# Callisto_Teknic_MSO_LSI_Relay_x_4.net
KiCad netlist of a schematic drawn in EAGLE
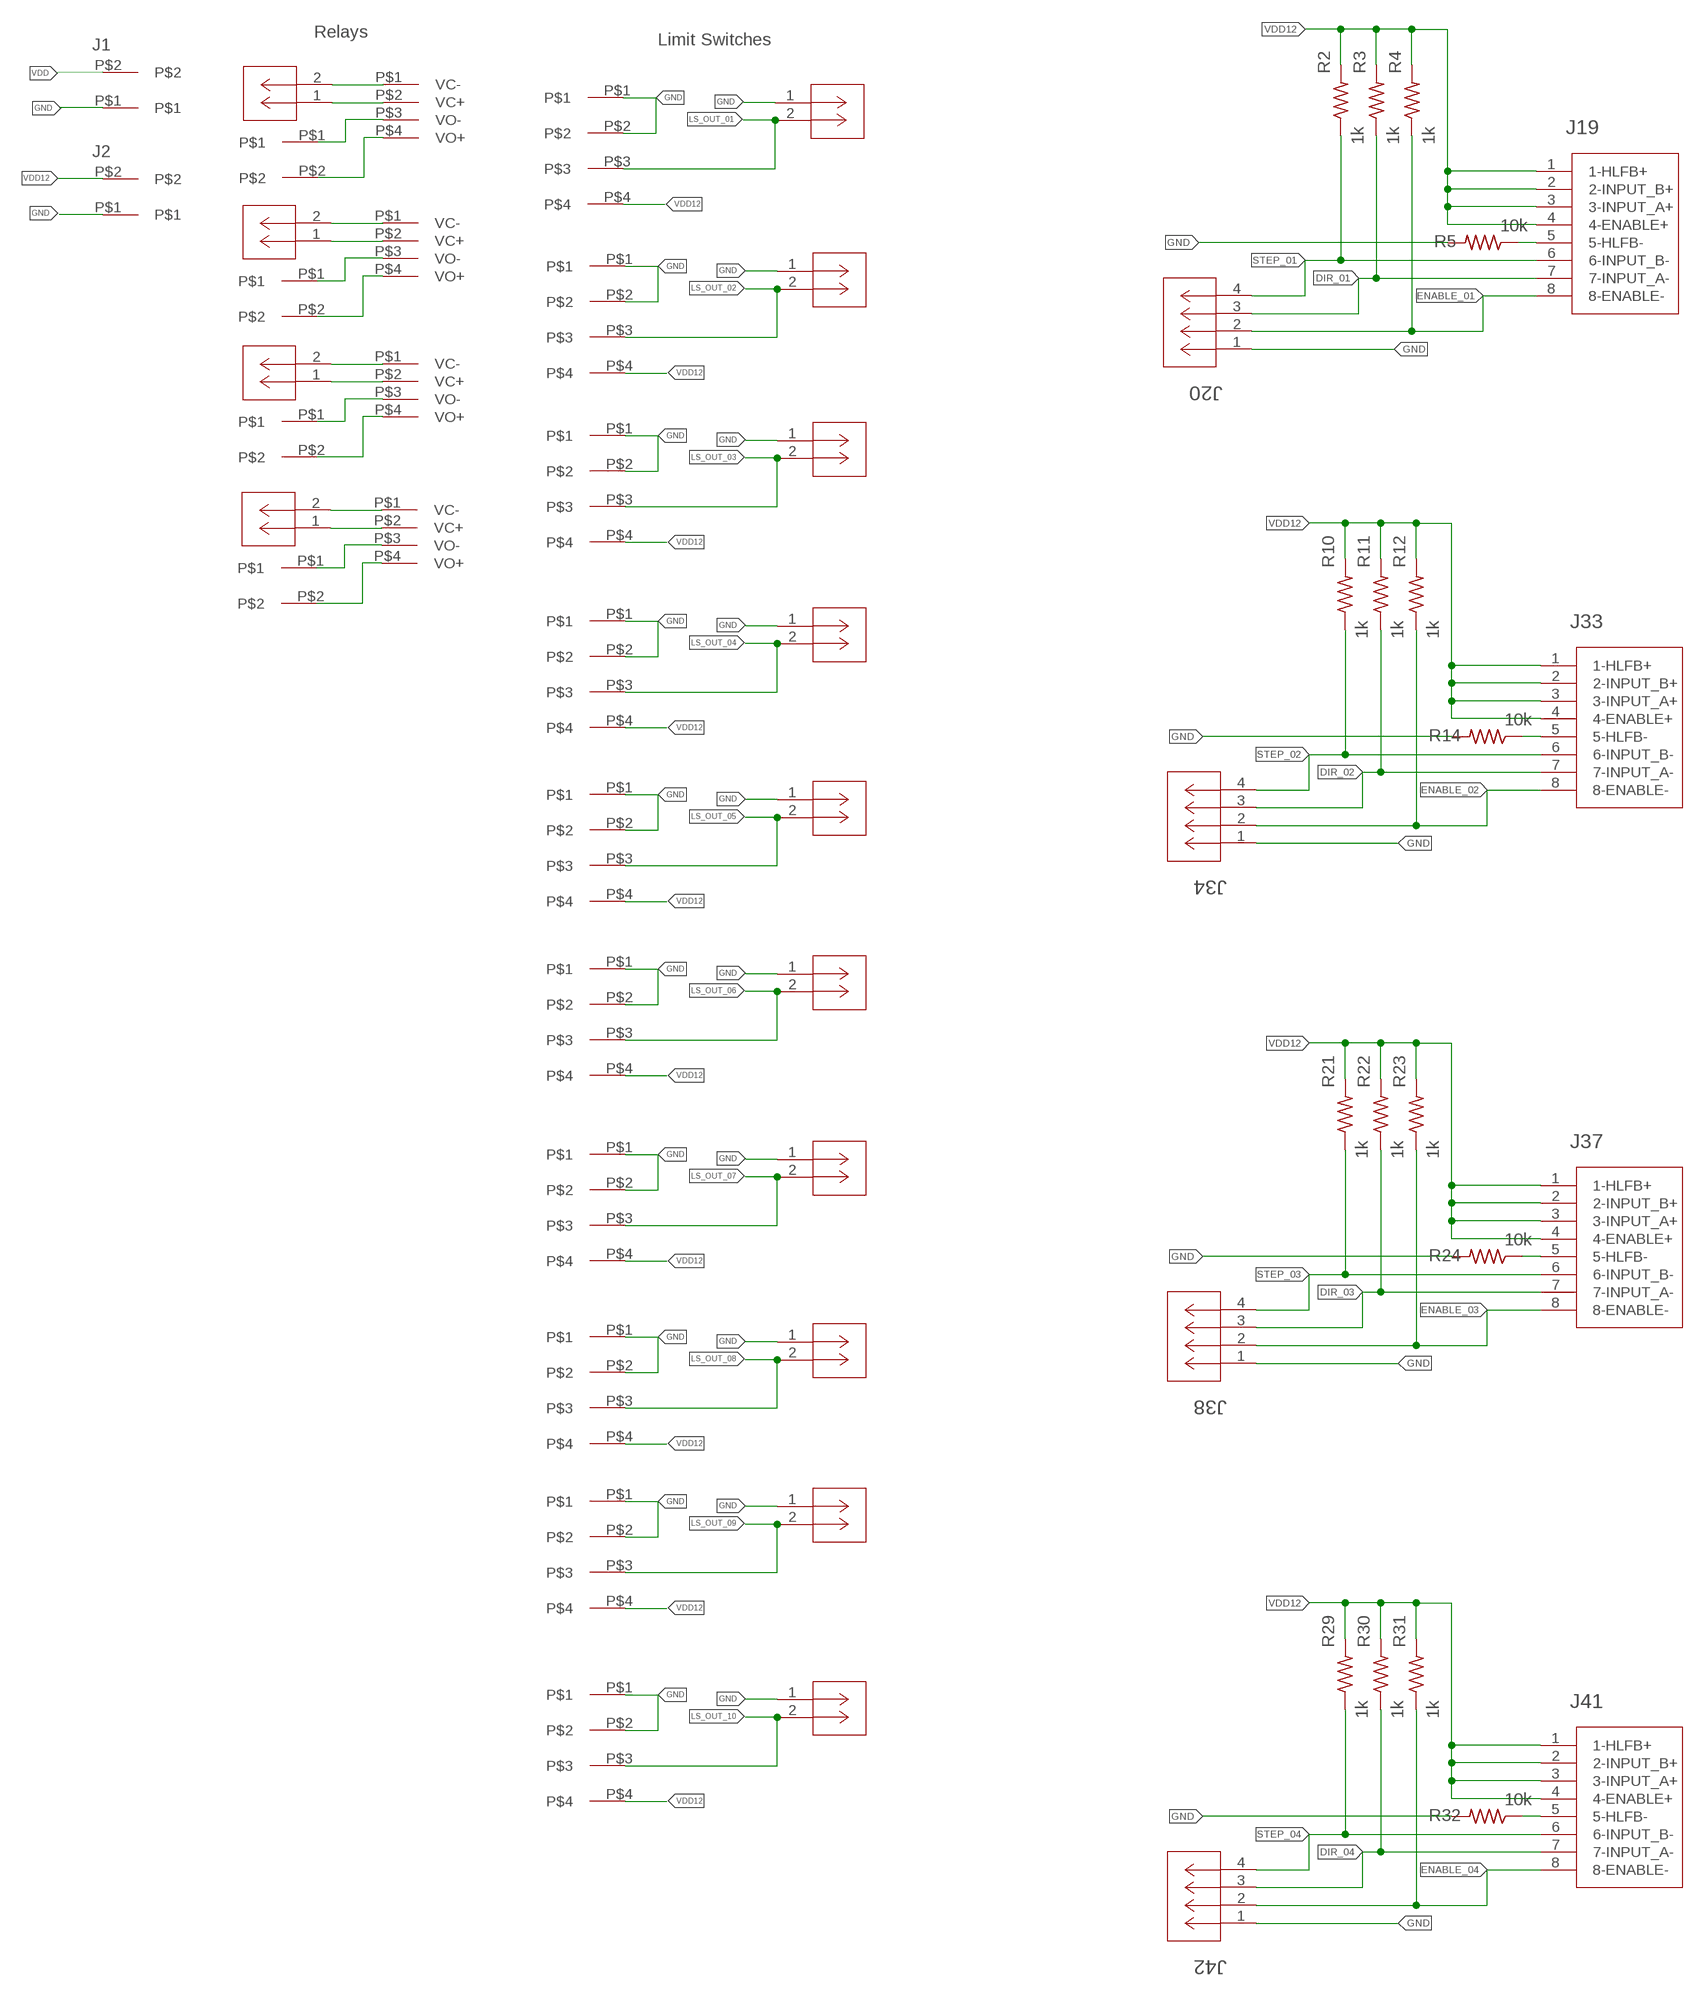
[diagram p0: schematic, sheet 1, part 1 of 2]
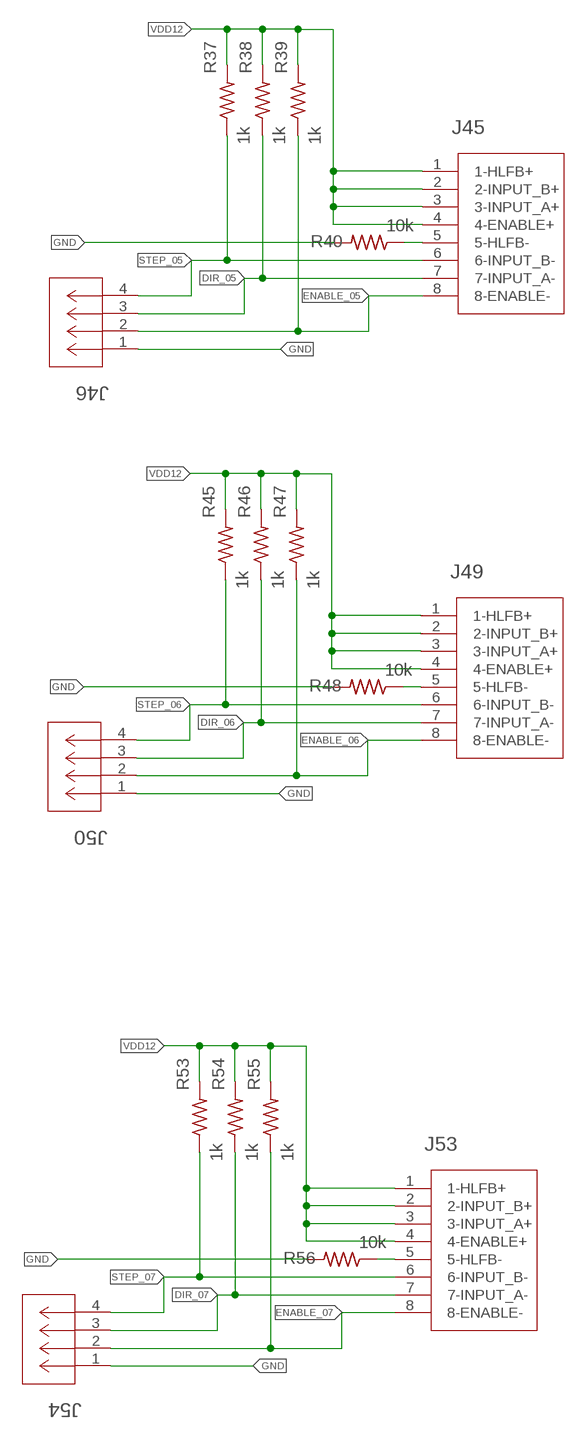
[diagram p1: schematic, sheet 1, part 2 of 2]

(export (version "E")
  (design (tool "Eeschema 10.0.6"))
  (components
    (comp (ref "J1")
      (value "2-pos")
      (footprint "eagle-import:2_3.81MM_PITCH")
      (fields (field (name "PARTNO") "691322310002"))
      (libsource (lib "eagle-import") (part "3.81MM_1_X_2_RT_ANGLE_PLUG_HEADER"))
    )
    (comp (ref "J2")
      (value "2-pos")
      (footprint "eagle-import:2_3.81MM_PITCH")
      (fields (field (name "PARTNO") "691322310002"))
      (libsource (lib "eagle-import") (part "3.81MM_1_X_2_RT_ANGLE_PLUG_HEADER"))
    )
    (comp (ref "J4")
      (value "CONN_530470210_PICOBLADE_X_2")
      (footprint "eagle-import:CON_530470210_MOL")
      (fields
        (field (name "MANUFACTURER_PART_NUMBER") "530470210")
        (field (name "COPYRIGHT") "Copyright (C) 2022 Ultra Librarian. All rights reserved.")
      )
      (libsource (lib "eagle-import") (part "CONN_530470210_PICOBLADE_X_2"))
    )
    (comp (ref "J5")
      (value "2-pos")
      (footprint "eagle-import:2_3.81MM_PITCH")
      (fields (field (name "PARTNO") "691322310002"))
      (libsource (lib "eagle-import") (part "3.81MM_1_X_2_RT_ANGLE_PLUG_HEADER"))
    )
    (comp (ref "J6")
      (value "CONN_530470210_PICOBLADE_X_2")
      (footprint "eagle-import:CON_530470210_MOL")
      (fields
        (field (name "MANUFACTURER_PART_NUMBER") "530470210")
        (field (name "COPYRIGHT") "Copyright (C) 2022 Ultra Librarian. All rights reserved.")
      )
      (libsource (lib "eagle-import") (part "CONN_530470210_PICOBLADE_X_2"))
    )
    (comp (ref "J7")
      (value "2-pos")
      (footprint "eagle-import:2_3.81MM_PITCH")
      (fields (field (name "PARTNO") "691322310002"))
      (libsource (lib "eagle-import") (part "3.81MM_1_X_2_RT_ANGLE_PLUG_HEADER"))
    )
    (comp (ref "J8")
      (value "CONN_530470210_PICOBLADE_X_2")
      (footprint "eagle-import:CON_530470210_MOL")
      (fields
        (field (name "MANUFACTURER_PART_NUMBER") "530470210")
        (field (name "COPYRIGHT") "Copyright (C) 2022 Ultra Librarian. All rights reserved.")
      )
      (libsource (lib "eagle-import") (part "CONN_530470210_PICOBLADE_X_2"))
    )
    (comp (ref "J9")
      (value "2-pos")
      (footprint "eagle-import:2_3.81MM_PITCH")
      (fields (field (name "PARTNO") "691322310002"))
      (libsource (lib "eagle-import") (part "3.81MM_1_X_2_RT_ANGLE_PLUG_HEADER"))
    )
    (comp (ref "J10")
      (value "CONN_530470210_PICOBLADE_X_2")
      (footprint "eagle-import:CON_530470210_MOL")
      (fields
        (field (name "MANUFACTURER_PART_NUMBER") "530470210")
        (field (name "COPYRIGHT") "Copyright (C) 2022 Ultra Librarian. All rights reserved.")
      )
      (libsource (lib "eagle-import") (part "CONN_530470210_PICOBLADE_X_2"))
    )
    (comp (ref "J11")
      (value "2-pos")
      (footprint "eagle-import:2_3.81MM_PITCH")
      (fields (field (name "PARTNO") "691322310002"))
      (libsource (lib "eagle-import") (part "3.81MM_1_X_2_RT_ANGLE_PLUG_HEADER"))
    )
    (comp (ref "J13")
      (value "CONN_530470210_PICOBLADE_X_2")
      (footprint "eagle-import:CON_530470210_MOL")
      (fields
        (field (name "MANUFACTURER_PART_NUMBER") "530470210")
        (field (name "COPYRIGHT") "Copyright (C) 2022 Ultra Librarian. All rights reserved.")
      )
      (libsource (lib "eagle-import") (part "CONN_530470210_PICOBLADE_X_2"))
    )
    (comp (ref "J14")
      (value "4-pos")
      (footprint "eagle-import:1X4_3.81MM_PITCH")
      (fields (field (name "PARTNO") "691322310004"))
      (libsource (lib "eagle-import") (part "3.81MM_1_X_4_RT_ANGLE_PLUG_HEADER"))
    )
    (comp (ref "J15")
      (value "CONN_530470210_PICOBLADE_X_2")
      (footprint "eagle-import:CON_530470210_MOL")
      (fields
        (field (name "MANUFACTURER_PART_NUMBER") "530470210")
        (field (name "COPYRIGHT") "Copyright (C) 2022 Ultra Librarian. All rights reserved.")
      )
      (libsource (lib "eagle-import") (part "CONN_530470210_PICOBLADE_X_2"))
    )
    (comp (ref "J16")
      (value "4-pos")
      (footprint "eagle-import:1X4_3.81MM_PITCH")
      (fields (field (name "PARTNO") "691322310004"))
      (libsource (lib "eagle-import") (part "3.81MM_1_X_4_RT_ANGLE_PLUG_HEADER"))
    )
    (comp (ref "J17")
      (value "CONN_530470210_PICOBLADE_X_2")
      (footprint "eagle-import:CON_530470210_MOL")
      (fields
        (field (name "MANUFACTURER_PART_NUMBER") "530470210")
        (field (name "COPYRIGHT") "Copyright (C) 2022 Ultra Librarian. All rights reserved.")
      )
      (libsource (lib "eagle-import") (part "CONN_530470210_PICOBLADE_X_2"))
    )
    (comp (ref "J18")
      (value "4-pos")
      (footprint "eagle-import:1X4_3.81MM_PITCH")
      (fields (field (name "PARTNO") "691322310004"))
      (libsource (lib "eagle-import") (part "3.81MM_1_X_4_RT_ANGLE_PLUG_HEADER"))
    )
    (comp (ref "J19")
      (value "TEKNIC_8PIN_MOTOR")
      (footprint "eagle-import:CON_39281083")
      (fields
        (field (name "MANUFACTURER_PART_NUMBER") "39281083")
        (field (name "COPYRIGHT") "Copyright (C) 2022 Ultra Librarian. All rights reserved.")
      )
      (libsource (lib "eagle-import") (part "TEKNIC_8PIN_MOTOR"))
    )
    (comp (ref "J20")
      (value "CONN_530470410_PICOBLADE_X_4")
      (footprint "eagle-import:CON_530470410_MOL")
      (fields
        (field (name "MANUFACTURER_PART_NUMBER") "530470410")
        (field (name "COPYRIGHT") "Copyright (C) 2022 Ultra Librarian. All rights reserved.")
      )
      (libsource (lib "eagle-import") (part "CONN_530470410_PICOBLADE_X_4"))
    )
    (comp (ref "J21")
      (value "CONN_530470210_PICOBLADE_X_2")
      (footprint "eagle-import:CON_530470210_MOL")
      (fields
        (field (name "MANUFACTURER_PART_NUMBER") "530470210")
        (field (name "COPYRIGHT") "Copyright (C) 2022 Ultra Librarian. All rights reserved.")
      )
      (libsource (lib "eagle-import") (part "CONN_530470210_PICOBLADE_X_2"))
    )
    (comp (ref "J22")
      (value "4-pos")
      (footprint "eagle-import:1X4_3.81MM_PITCH")
      (fields (field (name "PARTNO") "691322310004"))
      (libsource (lib "eagle-import") (part "3.81MM_1_X_4_RT_ANGLE_PLUG_HEADER"))
    )
    (comp (ref "J23")
      (value "CONN_530470210_PICOBLADE_X_2")
      (footprint "eagle-import:CON_530470210_MOL")
      (fields
        (field (name "MANUFACTURER_PART_NUMBER") "530470210")
        (field (name "COPYRIGHT") "Copyright (C) 2022 Ultra Librarian. All rights reserved.")
      )
      (libsource (lib "eagle-import") (part "CONN_530470210_PICOBLADE_X_2"))
    )
    (comp (ref "J24")
      (value "4-pos")
      (footprint "eagle-import:1X4_3.81MM_PITCH")
      (fields (field (name "PARTNO") "691322310004"))
      (libsource (lib "eagle-import") (part "3.81MM_1_X_4_RT_ANGLE_PLUG_HEADER"))
    )
    (comp (ref "J25")
      (value "CONN_530470210_PICOBLADE_X_2")
      (footprint "eagle-import:CON_530470210_MOL")
      (fields
        (field (name "MANUFACTURER_PART_NUMBER") "530470210")
        (field (name "COPYRIGHT") "Copyright (C) 2022 Ultra Librarian. All rights reserved.")
      )
      (libsource (lib "eagle-import") (part "CONN_530470210_PICOBLADE_X_2"))
    )
    (comp (ref "J26")
      (value "4-pos")
      (footprint "eagle-import:1X4_3.81MM_PITCH")
      (fields (field (name "PARTNO") "691322310004"))
      (libsource (lib "eagle-import") (part "3.81MM_1_X_4_RT_ANGLE_PLUG_HEADER"))
    )
    (comp (ref "J27")
      (value "CONN_530470210_PICOBLADE_X_2")
      (footprint "eagle-import:CON_530470210_MOL")
      (fields
        (field (name "MANUFACTURER_PART_NUMBER") "530470210")
        (field (name "COPYRIGHT") "Copyright (C) 2022 Ultra Librarian. All rights reserved.")
      )
      (libsource (lib "eagle-import") (part "CONN_530470210_PICOBLADE_X_2"))
    )
    (comp (ref "J28")
      (value "4-pos")
      (footprint "eagle-import:1X4_3.81MM_PITCH")
      (fields (field (name "PARTNO") "691322310004"))
      (libsource (lib "eagle-import") (part "3.81MM_1_X_4_RT_ANGLE_PLUG_HEADER"))
    )
    (comp (ref "J29")
      (value "CONN_530470210_PICOBLADE_X_2")
      (footprint "eagle-import:CON_530470210_MOL")
      (fields
        (field (name "MANUFACTURER_PART_NUMBER") "530470210")
        (field (name "COPYRIGHT") "Copyright (C) 2022 Ultra Librarian. All rights reserved.")
      )
      (libsource (lib "eagle-import") (part "CONN_530470210_PICOBLADE_X_2"))
    )
    (comp (ref "J30")
      (value "4-pos")
      (footprint "eagle-import:1X4_3.81MM_PITCH")
      (fields (field (name "PARTNO") "691322310004"))
      (libsource (lib "eagle-import") (part "3.81MM_1_X_4_RT_ANGLE_PLUG_HEADER"))
    )
    (comp (ref "J31")
      (value "CONN_530470210_PICOBLADE_X_2")
      (footprint "eagle-import:CON_530470210_MOL")
      (fields
        (field (name "MANUFACTURER_PART_NUMBER") "530470210")
        (field (name "COPYRIGHT") "Copyright (C) 2022 Ultra Librarian. All rights reserved.")
      )
      (libsource (lib "eagle-import") (part "CONN_530470210_PICOBLADE_X_2"))
    )
    (comp (ref "J32")
      (value "4-pos")
      (footprint "eagle-import:1X4_3.81MM_PITCH")
      (fields (field (name "PARTNO") "691322310004"))
      (libsource (lib "eagle-import") (part "3.81MM_1_X_4_RT_ANGLE_PLUG_HEADER"))
    )
    (comp (ref "J33")
      (value "TEKNIC_8PIN_MOTOR")
      (footprint "eagle-import:CON_39281083")
      (fields
        (field (name "MANUFACTURER_PART_NUMBER") "39281083")
        (field (name "COPYRIGHT") "Copyright (C) 2022 Ultra Librarian. All rights reserved.")
      )
      (libsource (lib "eagle-import") (part "TEKNIC_8PIN_MOTOR"))
    )
    (comp (ref "J34")
      (value "CONN_530470410_PICOBLADE_X_4")
      (footprint "eagle-import:CON_530470410_MOL")
      (fields
        (field (name "MANUFACTURER_PART_NUMBER") "530470410")
        (field (name "COPYRIGHT") "Copyright (C) 2022 Ultra Librarian. All rights reserved.")
      )
      (libsource (lib "eagle-import") (part "CONN_530470410_PICOBLADE_X_4"))
    )
    (comp (ref "J37")
      (value "TEKNIC_8PIN_MOTOR")
      (footprint "eagle-import:CON_39281083")
      (fields
        (field (name "MANUFACTURER_PART_NUMBER") "39281083")
        (field (name "COPYRIGHT") "Copyright (C) 2022 Ultra Librarian. All rights reserved.")
      )
      (libsource (lib "eagle-import") (part "TEKNIC_8PIN_MOTOR"))
    )
    (comp (ref "J38")
      (value "CONN_530470410_PICOBLADE_X_4")
      (footprint "eagle-import:CON_530470410_MOL")
      (fields
        (field (name "MANUFACTURER_PART_NUMBER") "530470410")
        (field (name "COPYRIGHT") "Copyright (C) 2022 Ultra Librarian. All rights reserved.")
      )
      (libsource (lib "eagle-import") (part "CONN_530470410_PICOBLADE_X_4"))
    )
    (comp (ref "J39")
      (value "CONN_530470210_PICOBLADE_X_2")
      (footprint "eagle-import:CON_530470210_MOL")
      (fields
        (field (name "MANUFACTURER_PART_NUMBER") "530470210")
        (field (name "COPYRIGHT") "Copyright (C) 2022 Ultra Librarian. All rights reserved.")
      )
      (libsource (lib "eagle-import") (part "CONN_530470210_PICOBLADE_X_2"))
    )
    (comp (ref "J40")
      (value "4-pos")
      (footprint "eagle-import:1X4_3.81MM_PITCH")
      (fields (field (name "PARTNO") "691322310004"))
      (libsource (lib "eagle-import") (part "3.81MM_1_X_4_RT_ANGLE_PLUG_HEADER"))
    )
    (comp (ref "J41")
      (value "TEKNIC_8PIN_MOTOR")
      (footprint "eagle-import:CON_39281083")
      (fields
        (field (name "MANUFACTURER_PART_NUMBER") "39281083")
        (field (name "COPYRIGHT") "Copyright (C) 2022 Ultra Librarian. All rights reserved.")
      )
      (libsource (lib "eagle-import") (part "TEKNIC_8PIN_MOTOR"))
    )
    (comp (ref "J42")
      (value "CONN_530470410_PICOBLADE_X_4")
      (footprint "eagle-import:CON_530470410_MOL")
      (fields
        (field (name "MANUFACTURER_PART_NUMBER") "530470410")
        (field (name "COPYRIGHT") "Copyright (C) 2022 Ultra Librarian. All rights reserved.")
      )
      (libsource (lib "eagle-import") (part "CONN_530470410_PICOBLADE_X_4"))
    )
    (comp (ref "J45")
      (value "TEKNIC_8PIN_MOTOR")
      (footprint "eagle-import:CON_39281083")
      (fields
        (field (name "MANUFACTURER_PART_NUMBER") "39281083")
        (field (name "COPYRIGHT") "Copyright (C) 2022 Ultra Librarian. All rights reserved.")
      )
      (libsource (lib "eagle-import") (part "TEKNIC_8PIN_MOTOR"))
    )
    (comp (ref "J46")
      (value "CONN_530470410_PICOBLADE_X_4")
      (footprint "eagle-import:CON_530470410_MOL")
      (fields
        (field (name "MANUFACTURER_PART_NUMBER") "530470410")
        (field (name "COPYRIGHT") "Copyright (C) 2022 Ultra Librarian. All rights reserved.")
      )
      (libsource (lib "eagle-import") (part "CONN_530470410_PICOBLADE_X_4"))
    )
    (comp (ref "J49")
      (value "TEKNIC_8PIN_MOTOR")
      (footprint "eagle-import:CON_39281083")
      (fields
        (field (name "MANUFACTURER_PART_NUMBER") "39281083")
        (field (name "COPYRIGHT") "Copyright (C) 2022 Ultra Librarian. All rights reserved.")
      )
      (libsource (lib "eagle-import") (part "TEKNIC_8PIN_MOTOR"))
    )
    (comp (ref "J50")
      (value "CONN_530470410_PICOBLADE_X_4")
      (footprint "eagle-import:CON_530470410_MOL")
      (fields
        (field (name "MANUFACTURER_PART_NUMBER") "530470410")
        (field (name "COPYRIGHT") "Copyright (C) 2022 Ultra Librarian. All rights reserved.")
      )
      (libsource (lib "eagle-import") (part "CONN_530470410_PICOBLADE_X_4"))
    )
    (comp (ref "J53")
      (value "TEKNIC_8PIN_MOTOR")
      (footprint "eagle-import:CON_39281083")
      (fields
        (field (name "MANUFACTURER_PART_NUMBER") "39281083")
        (field (name "COPYRIGHT") "Copyright (C) 2022 Ultra Librarian. All rights reserved.")
      )
      (libsource (lib "eagle-import") (part "TEKNIC_8PIN_MOTOR"))
    )
    (comp (ref "J54")
      (value "CONN_530470410_PICOBLADE_X_4")
      (footprint "eagle-import:CON_530470410_MOL")
      (fields
        (field (name "MANUFACTURER_PART_NUMBER") "530470410")
        (field (name "COPYRIGHT") "Copyright (C) 2022 Ultra Librarian. All rights reserved.")
      )
      (libsource (lib "eagle-import") (part "CONN_530470410_PICOBLADE_X_4"))
    )
    (comp (ref "R2")
      (value "1k")
      (footprint "eagle-import:0805")
      (libsource (lib "eagle-import") (part "R_0805"))
    )
    (comp (ref "R3")
      (value "1k")
      (footprint "eagle-import:0805")
      (libsource (lib "eagle-import") (part "R_0805"))
    )
    (comp (ref "R4")
      (value "1k")
      (footprint "eagle-import:0805")
      (libsource (lib "eagle-import") (part "R_0805"))
    )
    (comp (ref "R5")
      (value "10k")
      (footprint "eagle-import:0805")
      (libsource (lib "eagle-import") (part "R_0805"))
    )
    (comp (ref "R10")
      (value "1k")
      (footprint "eagle-import:0805")
      (libsource (lib "eagle-import") (part "R_0805"))
    )
    (comp (ref "R11")
      (value "1k")
      (footprint "eagle-import:0805")
      (libsource (lib "eagle-import") (part "R_0805"))
    )
    (comp (ref "R12")
      (value "1k")
      (footprint "eagle-import:0805")
      (libsource (lib "eagle-import") (part "R_0805"))
    )
    (comp (ref "R14")
      (value "10k")
      (footprint "eagle-import:0805")
      (libsource (lib "eagle-import") (part "R_0805"))
    )
    (comp (ref "R21")
      (value "1k")
      (footprint "eagle-import:0805")
      (libsource (lib "eagle-import") (part "R_0805"))
    )
    (comp (ref "R22")
      (value "1k")
      (footprint "eagle-import:0805")
      (libsource (lib "eagle-import") (part "R_0805"))
    )
    (comp (ref "R23")
      (value "1k")
      (footprint "eagle-import:0805")
      (libsource (lib "eagle-import") (part "R_0805"))
    )
    (comp (ref "R24")
      (value "10k")
      (footprint "eagle-import:0805")
      (libsource (lib "eagle-import") (part "R_0805"))
    )
    (comp (ref "R29")
      (value "1k")
      (footprint "eagle-import:0805")
      (libsource (lib "eagle-import") (part "R_0805"))
    )
    (comp (ref "R30")
      (value "1k")
      (footprint "eagle-import:0805")
      (libsource (lib "eagle-import") (part "R_0805"))
    )
    (comp (ref "R31")
      (value "1k")
      (footprint "eagle-import:0805")
      (libsource (lib "eagle-import") (part "R_0805"))
    )
    (comp (ref "R32")
      (value "10k")
      (footprint "eagle-import:0805")
      (libsource (lib "eagle-import") (part "R_0805"))
    )
    (comp (ref "R37")
      (value "1k")
      (footprint "eagle-import:0805")
      (libsource (lib "eagle-import") (part "R_0805"))
    )
    (comp (ref "R38")
      (value "1k")
      (footprint "eagle-import:0805")
      (libsource (lib "eagle-import") (part "R_0805"))
    )
    (comp (ref "R39")
      (value "1k")
      (footprint "eagle-import:0805")
      (libsource (lib "eagle-import") (part "R_0805"))
    )
    (comp (ref "R40")
      (value "10k")
      (footprint "eagle-import:0805")
      (libsource (lib "eagle-import") (part "R_0805"))
    )
    (comp (ref "R45")
      (value "1k")
      (footprint "eagle-import:0805")
      (libsource (lib "eagle-import") (part "R_0805"))
    )
    (comp (ref "R46")
      (value "1k")
      (footprint "eagle-import:0805")
      (libsource (lib "eagle-import") (part "R_0805"))
    )
    (comp (ref "R47")
      (value "1k")
      (footprint "eagle-import:0805")
      (libsource (lib "eagle-import") (part "R_0805"))
    )
    (comp (ref "R48")
      (value "10k")
      (footprint "eagle-import:0805")
      (libsource (lib "eagle-import") (part "R_0805"))
    )
    (comp (ref "R53")
      (value "1k")
      (footprint "eagle-import:0805")
      (libsource (lib "eagle-import") (part "R_0805"))
    )
    (comp (ref "R54")
      (value "1k")
      (footprint "eagle-import:0805")
      (libsource (lib "eagle-import") (part "R_0805"))
    )
    (comp (ref "R55")
      (value "1k")
      (footprint "eagle-import:0805")
      (libsource (lib "eagle-import") (part "R_0805"))
    )
    (comp (ref "R56")
      (value "10k")
      (footprint "eagle-import:0805")
      (libsource (lib "eagle-import") (part "R_0805"))
    )
    (comp (ref "U$1")
      (value "RELAY_KYOTO_KF0604D")
      (footprint "eagle-import:RELAY_KYOTO_KF0604D")
      (libsource (lib "eagle-import") (part "RELAY_KYOTO_KF0604D"))
    )
    (comp (ref "U$2")
      (value "RELAY_KYOTO_KF0604D")
      (footprint "eagle-import:RELAY_KYOTO_KF0604D")
      (libsource (lib "eagle-import") (part "RELAY_KYOTO_KF0604D"))
    )
    (comp (ref "U$3")
      (value "RELAY_KYOTO_KF0604D")
      (footprint "eagle-import:RELAY_KYOTO_KF0604D")
      (libsource (lib "eagle-import") (part "RELAY_KYOTO_KF0604D"))
    )
    (comp (ref "U$4")
      (value "RELAY_KYOTO_KF0604D")
      (footprint "eagle-import:RELAY_KYOTO_KF0604D")
      (libsource (lib "eagle-import") (part "RELAY_KYOTO_KF0604D"))
    )
  )
  (nets
    (net (code "1") (name "DIR_01") (class "Default")
      (node (ref "J19") (pin "7") (pinfunction "7-INPUT_A-_7") (pintype "passive"))
      (node (ref "J20") (pin "3") (pinfunction "3_3") (pintype "passive"))
      (node (ref "R3") (pin "1") (pinfunction "1_1") (pintype "passive"))
    )
    (net (code "2") (name "DIR_02") (class "Default")
      (node (ref "J33") (pin "7") (pinfunction "7-INPUT_A-_7") (pintype "passive"))
      (node (ref "J34") (pin "3") (pinfunction "3_3") (pintype "passive"))
      (node (ref "R11") (pin "1") (pinfunction "1_1") (pintype "passive"))
    )
    (net (code "3") (name "DIR_03") (class "Default")
      (node (ref "J37") (pin "7") (pinfunction "7-INPUT_A-_7") (pintype "passive"))
      (node (ref "J38") (pin "3") (pinfunction "3_3") (pintype "passive"))
      (node (ref "R22") (pin "1") (pinfunction "1_1") (pintype "passive"))
    )
    (net (code "4") (name "DIR_04") (class "Default")
      (node (ref "J41") (pin "7") (pinfunction "7-INPUT_A-_7") (pintype "passive"))
      (node (ref "J42") (pin "3") (pinfunction "3_3") (pintype "passive"))
      (node (ref "R30") (pin "1") (pinfunction "1_1") (pintype "passive"))
    )
    (net (code "5") (name "DIR_05") (class "Default")
      (node (ref "J45") (pin "7") (pinfunction "7-INPUT_A-_7") (pintype "passive"))
      (node (ref "J46") (pin "3") (pinfunction "3_3") (pintype "passive"))
      (node (ref "R38") (pin "1") (pinfunction "1_1") (pintype "passive"))
    )
    (net (code "6") (name "DIR_06") (class "Default")
      (node (ref "J49") (pin "7") (pinfunction "7-INPUT_A-_7") (pintype "passive"))
      (node (ref "J50") (pin "3") (pinfunction "3_3") (pintype "passive"))
      (node (ref "R46") (pin "1") (pinfunction "1_1") (pintype "passive"))
    )
    (net (code "7") (name "DIR_07") (class "Default")
      (node (ref "J53") (pin "7") (pinfunction "7-INPUT_A-_7") (pintype "passive"))
      (node (ref "J54") (pin "3") (pinfunction "3_3") (pintype "passive"))
      (node (ref "R54") (pin "1") (pinfunction "1_1") (pintype "passive"))
    )
    (net (code "8") (name "ENABLE_01") (class "Default")
      (node (ref "J19") (pin "8") (pinfunction "8-ENABLE-_8") (pintype "passive"))
      (node (ref "J20") (pin "2") (pinfunction "2_2") (pintype "passive"))
      (node (ref "R4") (pin "1") (pinfunction "1_1") (pintype "passive"))
    )
    (net (code "9") (name "ENABLE_02") (class "Default")
      (node (ref "J33") (pin "8") (pinfunction "8-ENABLE-_8") (pintype "passive"))
      (node (ref "J34") (pin "2") (pinfunction "2_2") (pintype "passive"))
      (node (ref "R12") (pin "1") (pinfunction "1_1") (pintype "passive"))
    )
    (net (code "10") (name "ENABLE_03") (class "Default")
      (node (ref "J37") (pin "8") (pinfunction "8-ENABLE-_8") (pintype "passive"))
      (node (ref "J38") (pin "2") (pinfunction "2_2") (pintype "passive"))
      (node (ref "R23") (pin "1") (pinfunction "1_1") (pintype "passive"))
    )
    (net (code "11") (name "ENABLE_04") (class "Default")
      (node (ref "J41") (pin "8") (pinfunction "8-ENABLE-_8") (pintype "passive"))
      (node (ref "J42") (pin "2") (pinfunction "2_2") (pintype "passive"))
      (node (ref "R31") (pin "1") (pinfunction "1_1") (pintype "passive"))
    )
    (net (code "12") (name "ENABLE_05") (class "Default")
      (node (ref "J45") (pin "8") (pinfunction "8-ENABLE-_8") (pintype "passive"))
      (node (ref "J46") (pin "2") (pinfunction "2_2") (pintype "passive"))
      (node (ref "R39") (pin "1") (pinfunction "1_1") (pintype "passive"))
    )
    (net (code "13") (name "ENABLE_06") (class "Default")
      (node (ref "J49") (pin "8") (pinfunction "8-ENABLE-_8") (pintype "passive"))
      (node (ref "J50") (pin "2") (pinfunction "2_2") (pintype "passive"))
      (node (ref "R47") (pin "1") (pinfunction "1_1") (pintype "passive"))
    )
    (net (code "14") (name "ENABLE_07") (class "Default")
      (node (ref "J53") (pin "8") (pinfunction "8-ENABLE-_8") (pintype "passive"))
      (node (ref "J54") (pin "2") (pinfunction "2_2") (pintype "passive"))
      (node (ref "R55") (pin "1") (pinfunction "1_1") (pintype "passive"))
    )
    (net (code "15") (name "GND") (class "Default")
      (node (ref "J1") (pin "P$1") (pinfunction "P$1_P$1") (pintype "bidirectional"))
      (node (ref "J13") (pin "1") (pinfunction "1_1") (pintype "passive"))
      (node (ref "J14") (pin "P$1") (pinfunction "P$1_P$1") (pintype "bidirectional"))
      (node (ref "J14") (pin "P$2") (pinfunction "P$2_P$2") (pintype "bidirectional"))
      (node (ref "J15") (pin "1") (pinfunction "1_1") (pintype "passive"))
      (node (ref "J16") (pin "P$1") (pinfunction "P$1_P$1") (pintype "bidirectional"))
      (node (ref "J16") (pin "P$2") (pinfunction "P$2_P$2") (pintype "bidirectional"))
      (node (ref "J17") (pin "1") (pinfunction "1_1") (pintype "passive"))
      (node (ref "J18") (pin "P$1") (pinfunction "P$1_P$1") (pintype "bidirectional"))
      (node (ref "J18") (pin "P$2") (pinfunction "P$2_P$2") (pintype "bidirectional"))
      (node (ref "J2") (pin "P$1") (pinfunction "P$1_P$1") (pintype "bidirectional"))
      (node (ref "J20") (pin "1") (pinfunction "1_1") (pintype "passive"))
      (node (ref "J21") (pin "1") (pinfunction "1_1") (pintype "passive"))
      (node (ref "J22") (pin "P$1") (pinfunction "P$1_P$1") (pintype "bidirectional"))
      (node (ref "J22") (pin "P$2") (pinfunction "P$2_P$2") (pintype "bidirectional"))
      (node (ref "J23") (pin "1") (pinfunction "1_1") (pintype "passive"))
      (node (ref "J24") (pin "P$1") (pinfunction "P$1_P$1") (pintype "bidirectional"))
      (node (ref "J24") (pin "P$2") (pinfunction "P$2_P$2") (pintype "bidirectional"))
      (node (ref "J25") (pin "1") (pinfunction "1_1") (pintype "passive"))
      (node (ref "J26") (pin "P$1") (pinfunction "P$1_P$1") (pintype "bidirectional"))
      (node (ref "J26") (pin "P$2") (pinfunction "P$2_P$2") (pintype "bidirectional"))
      (node (ref "J27") (pin "1") (pinfunction "1_1") (pintype "passive"))
      (node (ref "J28") (pin "P$1") (pinfunction "P$1_P$1") (pintype "bidirectional"))
      (node (ref "J28") (pin "P$2") (pinfunction "P$2_P$2") (pintype "bidirectional"))
      (node (ref "J29") (pin "1") (pinfunction "1_1") (pintype "passive"))
      (node (ref "J30") (pin "P$1") (pinfunction "P$1_P$1") (pintype "bidirectional"))
      (node (ref "J30") (pin "P$2") (pinfunction "P$2_P$2") (pintype "bidirectional"))
      (node (ref "J31") (pin "1") (pinfunction "1_1") (pintype "passive"))
      (node (ref "J32") (pin "P$1") (pinfunction "P$1_P$1") (pintype "bidirectional"))
      (node (ref "J32") (pin "P$2") (pinfunction "P$2_P$2") (pintype "bidirectional"))
      (node (ref "J34") (pin "1") (pinfunction "1_1") (pintype "passive"))
      (node (ref "J38") (pin "1") (pinfunction "1_1") (pintype "passive"))
      (node (ref "J39") (pin "1") (pinfunction "1_1") (pintype "passive"))
      (node (ref "J40") (pin "P$1") (pinfunction "P$1_P$1") (pintype "bidirectional"))
      (node (ref "J40") (pin "P$2") (pinfunction "P$2_P$2") (pintype "bidirectional"))
      (node (ref "J42") (pin "1") (pinfunction "1_1") (pintype "passive"))
      (node (ref "J46") (pin "1") (pinfunction "1_1") (pintype "passive"))
      (node (ref "J50") (pin "1") (pinfunction "1_1") (pintype "passive"))
      (node (ref "J54") (pin "1") (pinfunction "1_1") (pintype "passive"))
      (node (ref "R14") (pin "2") (pinfunction "2_2") (pintype "passive"))
      (node (ref "R24") (pin "2") (pinfunction "2_2") (pintype "passive"))
      (node (ref "R32") (pin "2") (pinfunction "2_2") (pintype "passive"))
      (node (ref "R40") (pin "2") (pinfunction "2_2") (pintype "passive"))
      (node (ref "R48") (pin "2") (pinfunction "2_2") (pintype "passive"))
      (node (ref "R5") (pin "2") (pinfunction "2_2") (pintype "passive"))
      (node (ref "R56") (pin "2") (pinfunction "2_2") (pintype "passive"))
    )
    (net (code "16") (name "LS_OUT_01") (class "Default")
      (node (ref "J13") (pin "2") (pinfunction "2_2") (pintype "passive"))
      (node (ref "J14") (pin "P$3") (pinfunction "P$3_P$3") (pintype "bidirectional"))
    )
    (net (code "17") (name "LS_OUT_02") (class "Default")
      (node (ref "J17") (pin "2") (pinfunction "2_2") (pintype "passive"))
      (node (ref "J18") (pin "P$3") (pinfunction "P$3_P$3") (pintype "bidirectional"))
    )
    (net (code "18") (name "LS_OUT_03") (class "Default")
      (node (ref "J21") (pin "2") (pinfunction "2_2") (pintype "passive"))
      (node (ref "J22") (pin "P$3") (pinfunction "P$3_P$3") (pintype "bidirectional"))
    )
    (net (code "19") (name "LS_OUT_04") (class "Default")
      (node (ref "J25") (pin "2") (pinfunction "2_2") (pintype "passive"))
      (node (ref "J26") (pin "P$3") (pinfunction "P$3_P$3") (pintype "bidirectional"))
    )
    (net (code "20") (name "LS_OUT_05") (class "Default")
      (node (ref "J29") (pin "2") (pinfunction "2_2") (pintype "passive"))
      (node (ref "J30") (pin "P$3") (pinfunction "P$3_P$3") (pintype "bidirectional"))
    )
    (net (code "21") (name "LS_OUT_06") (class "Default")
      (node (ref "J15") (pin "2") (pinfunction "2_2") (pintype "passive"))
      (node (ref "J16") (pin "P$3") (pinfunction "P$3_P$3") (pintype "bidirectional"))
    )
    (net (code "22") (name "LS_OUT_07") (class "Default")
      (node (ref "J23") (pin "2") (pinfunction "2_2") (pintype "passive"))
      (node (ref "J24") (pin "P$3") (pinfunction "P$3_P$3") (pintype "bidirectional"))
    )
    (net (code "23") (name "LS_OUT_08") (class "Default")
      (node (ref "J27") (pin "2") (pinfunction "2_2") (pintype "passive"))
      (node (ref "J28") (pin "P$3") (pinfunction "P$3_P$3") (pintype "bidirectional"))
    )
    (net (code "24") (name "LS_OUT_09") (class "Default")
      (node (ref "J31") (pin "2") (pinfunction "2_2") (pintype "passive"))
      (node (ref "J32") (pin "P$3") (pinfunction "P$3_P$3") (pintype "bidirectional"))
    )
    (net (code "25") (name "LS_OUT_10") (class "Default")
      (node (ref "J39") (pin "2") (pinfunction "2_2") (pintype "passive"))
      (node (ref "J40") (pin "P$3") (pinfunction "P$3_P$3") (pintype "bidirectional"))
    )
    (net (code "26") (name "Net-(J19-5-HLFB-)") (class "Default")
      (node (ref "J19") (pin "5") (pinfunction "5-HLFB-_5") (pintype "passive"))
      (node (ref "R5") (pin "1") (pinfunction "1_1") (pintype "passive"))
    )
    (net (code "27") (name "Net-(J33-5-HLFB-)") (class "Default")
      (node (ref "J33") (pin "5") (pinfunction "5-HLFB-_5") (pintype "passive"))
      (node (ref "R14") (pin "1") (pinfunction "1_1") (pintype "passive"))
    )
    (net (code "28") (name "Net-(J37-5-HLFB-)") (class "Default")
      (node (ref "J37") (pin "5") (pinfunction "5-HLFB-_5") (pintype "passive"))
      (node (ref "R24") (pin "1") (pinfunction "1_1") (pintype "passive"))
    )
    (net (code "29") (name "Net-(J41-5-HLFB-)") (class "Default")
      (node (ref "J41") (pin "5") (pinfunction "5-HLFB-_5") (pintype "passive"))
      (node (ref "R32") (pin "1") (pinfunction "1_1") (pintype "passive"))
    )
    (net (code "30") (name "Net-(J45-5-HLFB-)") (class "Default")
      (node (ref "J45") (pin "5") (pinfunction "5-HLFB-_5") (pintype "passive"))
      (node (ref "R40") (pin "1") (pinfunction "1_1") (pintype "passive"))
    )
    (net (code "31") (name "Net-(J49-5-HLFB-)") (class "Default")
      (node (ref "J49") (pin "5") (pinfunction "5-HLFB-_5") (pintype "passive"))
      (node (ref "R48") (pin "1") (pinfunction "1_1") (pintype "passive"))
    )
    (net (code "32") (name "Net-(J53-5-HLFB-)") (class "Default")
      (node (ref "J53") (pin "5") (pinfunction "5-HLFB-_5") (pintype "passive"))
      (node (ref "R56") (pin "1") (pinfunction "1_1") (pintype "passive"))
    )
    (net (code "33") (name "Net-(U$1-VC+)") (class "Default")
      (node (ref "J4") (pin "1") (pinfunction "1_1") (pintype "passive"))
      (node (ref "U$1") (pin "P$2") (pinfunction "VC+_P$2") (pintype "bidirectional"))
    )
    (net (code "34") (name "Net-(U$1-VC-)") (class "Default")
      (node (ref "J4") (pin "2") (pinfunction "2_2") (pintype "passive"))
      (node (ref "U$1") (pin "P$1") (pinfunction "VC-_P$1") (pintype "bidirectional"))
    )
    (net (code "35") (name "Net-(U$1-VO+)") (class "Default")
      (node (ref "J5") (pin "P$2") (pinfunction "P$2_P$2") (pintype "bidirectional"))
      (node (ref "U$1") (pin "P$4") (pinfunction "VO+_P$4") (pintype "bidirectional"))
    )
    (net (code "36") (name "Net-(U$1-VO-)") (class "Default")
      (node (ref "J5") (pin "P$1") (pinfunction "P$1_P$1") (pintype "bidirectional"))
      (node (ref "U$1") (pin "P$3") (pinfunction "VO-_P$3") (pintype "bidirectional"))
    )
    (net (code "37") (name "Net-(U$2-VC+)") (class "Default")
      (node (ref "J6") (pin "1") (pinfunction "1_1") (pintype "passive"))
      (node (ref "U$2") (pin "P$2") (pinfunction "VC+_P$2") (pintype "bidirectional"))
    )
    (net (code "38") (name "Net-(U$2-VC-)") (class "Default")
      (node (ref "J6") (pin "2") (pinfunction "2_2") (pintype "passive"))
      (node (ref "U$2") (pin "P$1") (pinfunction "VC-_P$1") (pintype "bidirectional"))
    )
    (net (code "39") (name "Net-(U$2-VO+)") (class "Default")
      (node (ref "J7") (pin "P$2") (pinfunction "P$2_P$2") (pintype "bidirectional"))
      (node (ref "U$2") (pin "P$4") (pinfunction "VO+_P$4") (pintype "bidirectional"))
    )
    (net (code "40") (name "Net-(U$2-VO-)") (class "Default")
      (node (ref "J7") (pin "P$1") (pinfunction "P$1_P$1") (pintype "bidirectional"))
      (node (ref "U$2") (pin "P$3") (pinfunction "VO-_P$3") (pintype "bidirectional"))
    )
    (net (code "41") (name "Net-(U$3-VC+)") (class "Default")
      (node (ref "J8") (pin "1") (pinfunction "1_1") (pintype "passive"))
      (node (ref "U$3") (pin "P$2") (pinfunction "VC+_P$2") (pintype "bidirectional"))
    )
    (net (code "42") (name "Net-(U$3-VC-)") (class "Default")
      (node (ref "J8") (pin "2") (pinfunction "2_2") (pintype "passive"))
      (node (ref "U$3") (pin "P$1") (pinfunction "VC-_P$1") (pintype "bidirectional"))
    )
    (net (code "43") (name "Net-(U$3-VO+)") (class "Default")
      (node (ref "J9") (pin "P$2") (pinfunction "P$2_P$2") (pintype "bidirectional"))
      (node (ref "U$3") (pin "P$4") (pinfunction "VO+_P$4") (pintype "bidirectional"))
    )
    (net (code "44") (name "Net-(U$3-VO-)") (class "Default")
      (node (ref "J9") (pin "P$1") (pinfunction "P$1_P$1") (pintype "bidirectional"))
      (node (ref "U$3") (pin "P$3") (pinfunction "VO-_P$3") (pintype "bidirectional"))
    )
    (net (code "45") (name "Net-(U$4-VC+)") (class "Default")
      (node (ref "J10") (pin "1") (pinfunction "1_1") (pintype "passive"))
      (node (ref "U$4") (pin "P$2") (pinfunction "VC+_P$2") (pintype "bidirectional"))
    )
    (net (code "46") (name "Net-(U$4-VC-)") (class "Default")
      (node (ref "J10") (pin "2") (pinfunction "2_2") (pintype "passive"))
      (node (ref "U$4") (pin "P$1") (pinfunction "VC-_P$1") (pintype "bidirectional"))
    )
    (net (code "47") (name "Net-(U$4-VO+)") (class "Default")
      (node (ref "J11") (pin "P$2") (pinfunction "P$2_P$2") (pintype "bidirectional"))
      (node (ref "U$4") (pin "P$4") (pinfunction "VO+_P$4") (pintype "bidirectional"))
    )
    (net (code "48") (name "Net-(U$4-VO-)") (class "Default")
      (node (ref "J11") (pin "P$1") (pinfunction "P$1_P$1") (pintype "bidirectional"))
      (node (ref "U$4") (pin "P$3") (pinfunction "VO-_P$3") (pintype "bidirectional"))
    )
    (net (code "49") (name "STEP_01") (class "Default")
      (node (ref "J19") (pin "6") (pinfunction "6-INPUT_B-_6") (pintype "passive"))
      (node (ref "J20") (pin "4") (pinfunction "4_4") (pintype "passive"))
      (node (ref "R2") (pin "1") (pinfunction "1_1") (pintype "passive"))
    )
    (net (code "50") (name "STEP_02") (class "Default")
      (node (ref "J33") (pin "6") (pinfunction "6-INPUT_B-_6") (pintype "passive"))
      (node (ref "J34") (pin "4") (pinfunction "4_4") (pintype "passive"))
      (node (ref "R10") (pin "1") (pinfunction "1_1") (pintype "passive"))
    )
    (net (code "51") (name "STEP_03") (class "Default")
      (node (ref "J37") (pin "6") (pinfunction "6-INPUT_B-_6") (pintype "passive"))
      (node (ref "J38") (pin "4") (pinfunction "4_4") (pintype "passive"))
      (node (ref "R21") (pin "1") (pinfunction "1_1") (pintype "passive"))
    )
    (net (code "52") (name "STEP_04") (class "Default")
      (node (ref "J41") (pin "6") (pinfunction "6-INPUT_B-_6") (pintype "passive"))
      (node (ref "J42") (pin "4") (pinfunction "4_4") (pintype "passive"))
      (node (ref "R29") (pin "1") (pinfunction "1_1") (pintype "passive"))
    )
    (net (code "53") (name "STEP_05") (class "Default")
      (node (ref "J45") (pin "6") (pinfunction "6-INPUT_B-_6") (pintype "passive"))
      (node (ref "J46") (pin "4") (pinfunction "4_4") (pintype "passive"))
      (node (ref "R37") (pin "1") (pinfunction "1_1") (pintype "passive"))
    )
    (net (code "54") (name "STEP_06") (class "Default")
      (node (ref "J49") (pin "6") (pinfunction "6-INPUT_B-_6") (pintype "passive"))
      (node (ref "J50") (pin "4") (pinfunction "4_4") (pintype "passive"))
      (node (ref "R45") (pin "1") (pinfunction "1_1") (pintype "passive"))
    )
    (net (code "55") (name "STEP_07") (class "Default")
      (node (ref "J53") (pin "6") (pinfunction "6-INPUT_B-_6") (pintype "passive"))
      (node (ref "J54") (pin "4") (pinfunction "4_4") (pintype "passive"))
      (node (ref "R53") (pin "1") (pinfunction "1_1") (pintype "passive"))
    )
    (net (code "56") (name "VDD") (class "Default")
      (node (ref "J1") (pin "P$2") (pinfunction "P$2_P$2") (pintype "bidirectional"))
    )
    (net (code "57") (name "VDD12") (class "Default")
      (node (ref "J14") (pin "P$4") (pinfunction "P$4_P$4") (pintype "bidirectional"))
      (node (ref "J16") (pin "P$4") (pinfunction "P$4_P$4") (pintype "bidirectional"))
      (node (ref "J18") (pin "P$4") (pinfunction "P$4_P$4") (pintype "bidirectional"))
      (node (ref "J19") (pin "1") (pinfunction "1-HLFB+_1") (pintype "passive"))
      (node (ref "J19") (pin "2") (pinfunction "2-INPUT_B+_2") (pintype "passive"))
      (node (ref "J19") (pin "3") (pinfunction "3-INPUT_A+_3") (pintype "passive"))
      (node (ref "J19") (pin "4") (pinfunction "4-ENABLE+_4") (pintype "passive"))
      (node (ref "J2") (pin "P$2") (pinfunction "P$2_P$2") (pintype "bidirectional"))
      (node (ref "J22") (pin "P$4") (pinfunction "P$4_P$4") (pintype "bidirectional"))
      (node (ref "J24") (pin "P$4") (pinfunction "P$4_P$4") (pintype "bidirectional"))
      (node (ref "J26") (pin "P$4") (pinfunction "P$4_P$4") (pintype "bidirectional"))
      (node (ref "J28") (pin "P$4") (pinfunction "P$4_P$4") (pintype "bidirectional"))
      (node (ref "J30") (pin "P$4") (pinfunction "P$4_P$4") (pintype "bidirectional"))
      (node (ref "J32") (pin "P$4") (pinfunction "P$4_P$4") (pintype "bidirectional"))
      (node (ref "J33") (pin "1") (pinfunction "1-HLFB+_1") (pintype "passive"))
      (node (ref "J33") (pin "2") (pinfunction "2-INPUT_B+_2") (pintype "passive"))
      (node (ref "J33") (pin "3") (pinfunction "3-INPUT_A+_3") (pintype "passive"))
      (node (ref "J33") (pin "4") (pinfunction "4-ENABLE+_4") (pintype "passive"))
      (node (ref "J37") (pin "1") (pinfunction "1-HLFB+_1") (pintype "passive"))
      (node (ref "J37") (pin "2") (pinfunction "2-INPUT_B+_2") (pintype "passive"))
      (node (ref "J37") (pin "3") (pinfunction "3-INPUT_A+_3") (pintype "passive"))
      (node (ref "J37") (pin "4") (pinfunction "4-ENABLE+_4") (pintype "passive"))
      (node (ref "J40") (pin "P$4") (pinfunction "P$4_P$4") (pintype "bidirectional"))
      (node (ref "J41") (pin "1") (pinfunction "1-HLFB+_1") (pintype "passive"))
      (node (ref "J41") (pin "2") (pinfunction "2-INPUT_B+_2") (pintype "passive"))
      (node (ref "J41") (pin "3") (pinfunction "3-INPUT_A+_3") (pintype "passive"))
      (node (ref "J41") (pin "4") (pinfunction "4-ENABLE+_4") (pintype "passive"))
      (node (ref "J45") (pin "1") (pinfunction "1-HLFB+_1") (pintype "passive"))
      (node (ref "J45") (pin "2") (pinfunction "2-INPUT_B+_2") (pintype "passive"))
      (node (ref "J45") (pin "3") (pinfunction "3-INPUT_A+_3") (pintype "passive"))
      (node (ref "J45") (pin "4") (pinfunction "4-ENABLE+_4") (pintype "passive"))
      (node (ref "J49") (pin "1") (pinfunction "1-HLFB+_1") (pintype "passive"))
      (node (ref "J49") (pin "2") (pinfunction "2-INPUT_B+_2") (pintype "passive"))
      (node (ref "J49") (pin "3") (pinfunction "3-INPUT_A+_3") (pintype "passive"))
      (node (ref "J49") (pin "4") (pinfunction "4-ENABLE+_4") (pintype "passive"))
      (node (ref "J53") (pin "1") (pinfunction "1-HLFB+_1") (pintype "passive"))
      (node (ref "J53") (pin "2") (pinfunction "2-INPUT_B+_2") (pintype "passive"))
      (node (ref "J53") (pin "3") (pinfunction "3-INPUT_A+_3") (pintype "passive"))
      (node (ref "J53") (pin "4") (pinfunction "4-ENABLE+_4") (pintype "passive"))
      (node (ref "R10") (pin "2") (pinfunction "2_2") (pintype "passive"))
      (node (ref "R11") (pin "2") (pinfunction "2_2") (pintype "passive"))
      (node (ref "R12") (pin "2") (pinfunction "2_2") (pintype "passive"))
      (node (ref "R2") (pin "2") (pinfunction "2_2") (pintype "passive"))
      (node (ref "R21") (pin "2") (pinfunction "2_2") (pintype "passive"))
      (node (ref "R22") (pin "2") (pinfunction "2_2") (pintype "passive"))
      (node (ref "R23") (pin "2") (pinfunction "2_2") (pintype "passive"))
      (node (ref "R29") (pin "2") (pinfunction "2_2") (pintype "passive"))
      (node (ref "R3") (pin "2") (pinfunction "2_2") (pintype "passive"))
      (node (ref "R30") (pin "2") (pinfunction "2_2") (pintype "passive"))
      (node (ref "R31") (pin "2") (pinfunction "2_2") (pintype "passive"))
      (node (ref "R37") (pin "2") (pinfunction "2_2") (pintype "passive"))
      (node (ref "R38") (pin "2") (pinfunction "2_2") (pintype "passive"))
      (node (ref "R39") (pin "2") (pinfunction "2_2") (pintype "passive"))
      (node (ref "R4") (pin "2") (pinfunction "2_2") (pintype "passive"))
      (node (ref "R45") (pin "2") (pinfunction "2_2") (pintype "passive"))
      (node (ref "R46") (pin "2") (pinfunction "2_2") (pintype "passive"))
      (node (ref "R47") (pin "2") (pinfunction "2_2") (pintype "passive"))
      (node (ref "R53") (pin "2") (pinfunction "2_2") (pintype "passive"))
      (node (ref "R54") (pin "2") (pinfunction "2_2") (pintype "passive"))
      (node (ref "R55") (pin "2") (pinfunction "2_2") (pintype "passive"))
    )
  )
)
